# Power.net
KiCad netlist of a schematic drawn in Altium Designer
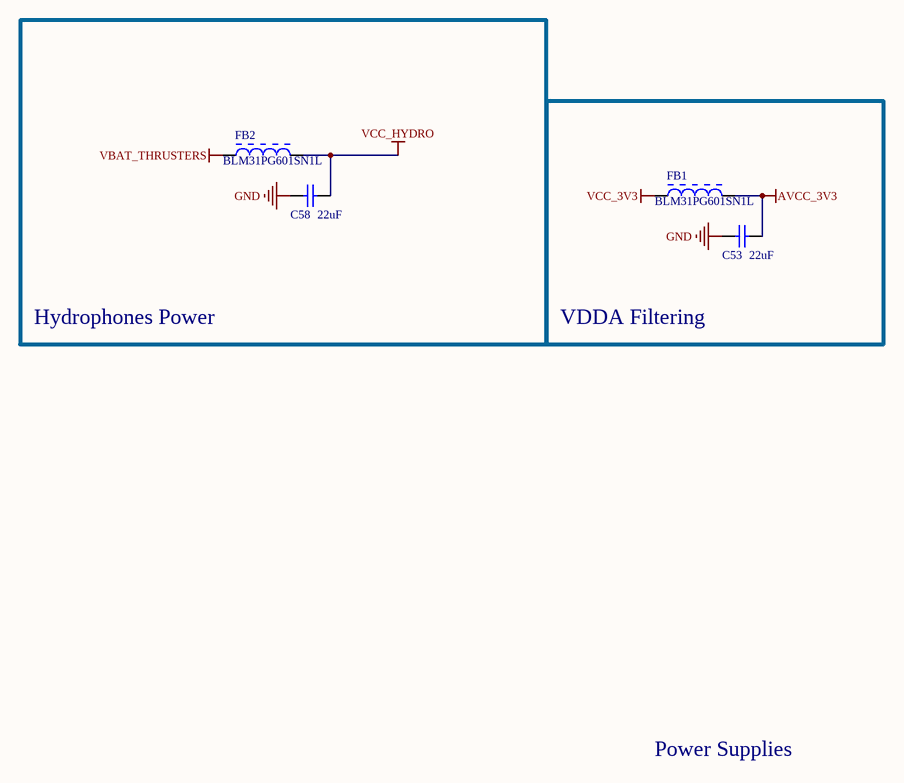
[diagram p0: Power.SchDoc]

(export (version "E")
  (design (tool "Eeschema 10.0.6"))
  (components
    (comp (ref "C53")
      (value "22uF")
      (footprint "CAPC1210(3225)100_N")
      (description "CAP 22nF 16V ±5% 1210 (3225 Metric) Thickness 1mm SMD")
      (fields (field (name "TOLERANCE") "±20%"))
      (libsource (lib "Altium Content Vault") (part "CMP-1038-01290-1"))
    )
    (comp (ref "C58")
      (value "22uF")
      (footprint "CAPC1210(3225)100_N")
      (description "CAP 22nF 16V ±5% 1210 (3225 Metric) Thickness 1mm SMD")
      (fields (field (name "TOLERANCE") "±20%"))
      (libsource (lib "Altium Content Vault") (part "CMP-1038-01290-1"))
    )
    (comp (ref "FB1")
      (value "BLM31PG601SN1L")
      (footprint "MURA-BLM31-B-CHIP-2_V")
      (fields (field (name "MANUFACTURER") "Murata"))
      (libsource (lib "Altium Content Vault") (part "MURA-FB-2"))
    )
    (comp (ref "FB2")
      (value "BLM31PG601SN1L")
      (footprint "MURA-BLM31-B-CHIP-2_V")
      (fields (field (name "MANUFACTURER") "Murata"))
      (libsource (lib "Altium Content Vault") (part "MURA-FB-2"))
    )
  )
  (nets
    (net (code "1") (name "AVCC_3V3") (class "Default")
      (node (ref "C53") (pin "1") (pinfunction "1_1") (pintype "passive"))
      (node (ref "FB1") (pin "2") (pinfunction "2_2") (pintype "passive"))
    )
    (net (code "2") (name "GND") (class "Default")
      (node (ref "C53") (pin "2") (pinfunction "2_2") (pintype "passive"))
      (node (ref "C58") (pin "2") (pinfunction "2_2") (pintype "passive"))
    )
    (net (code "3") (name "VBAT_THRUSTERS") (class "Default")
      (node (ref "FB2") (pin "1") (pinfunction "1_1") (pintype "passive"))
    )
    (net (code "4") (name "VCC_3V3") (class "Default")
      (node (ref "FB1") (pin "1") (pinfunction "1_1") (pintype "passive"))
    )
    (net (code "5") (name "VCC_HYDRO") (class "Default")
      (node (ref "C58") (pin "1") (pinfunction "1_1") (pintype "passive"))
      (node (ref "FB2") (pin "2") (pinfunction "2_2") (pintype "passive"))
    )
  )
)
